# clock.net
KiCad netlist of a schematic drawn in Altium Designer
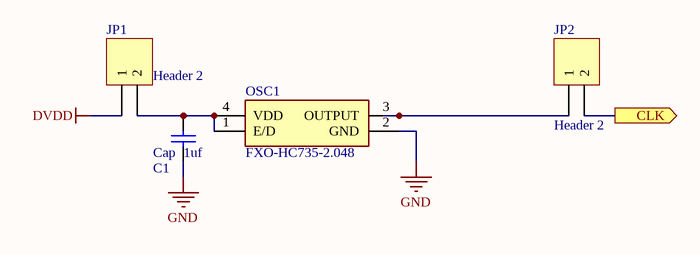
[diagram p0: clock.SchDoc]

(export (version "E")
  (design (tool "Eeschema 10.0.6"))
  (components
    (comp (ref "C1")
      (value "Cap")
      (footprint "1608[0603]")
      (description "Capacitor")
      (fields (field (name "ALTIUM_VALUE") "1uf") (field (name "PUBLISHER") "Altium Limited"))
      (libsource (lib "Miscellaneous Devices") (part "Cap"))
    )
    (comp (ref "JP1")
      (value "Header 2")
      (footprint "HDR1X2")
      (description "Header, 2-Pin")
      (fields (field (name "PUBLISHER") "Altium Limited"))
      (libsource (lib "Miscellaneous Connectors") (part "Header 2"))
    )
    (comp (ref "JP2")
      (value "Header 2")
      (footprint "HDR1X2")
      (description "Header, 2-Pin")
      (fields (field (name "PUBLISHER") "Altium Limited"))
      (libsource (lib "Miscellaneous Connectors") (part "Header 2"))
    )
    (comp (ref "OSC1")
      (value "FXO-HC735-2.048")
      (footprint "FXO-HC736R-40")
      (description "Crystal or Oscillator")
      (fields (field (name "MOUSER PART NUMBER") "XPO-HC735-2.048"))
      (libsource (lib "*") (part "FXO-HC735-2.048"))
    )
  )
  (nets
    (net (code "1") (name "/CLK") (class "Default")
      (node (ref "JP2") (pin "2") (pinfunction "2_2") (pintype "passive"))
    )
    (net (code "2") (name "DVDD") (class "Default")
      (node (ref "JP1") (pin "1") (pinfunction "1_1") (pintype "passive"))
    )
    (net (code "3") (name "GND") (class "Default")
      (node (ref "C1") (pin "1") (pinfunction "1_1") (pintype "passive"))
      (node (ref "OSC1") (pin "2") (pinfunction "GND_2") (pintype "passive"))
    )
    (net (code "4") (name "Net-(OSC1-E{slash}D)") (class "Default")
      (node (ref "C1") (pin "2") (pinfunction "2_2") (pintype "passive"))
      (node (ref "JP1") (pin "2") (pinfunction "2_2") (pintype "passive"))
      (node (ref "OSC1") (pin "1") (pinfunction "E/D_1") (pintype "passive"))
      (node (ref "OSC1") (pin "4") (pinfunction "VDD_4") (pintype "passive"))
    )
    (net (code "5") (name "Net-(OSC1-OUTPUT)") (class "Default")
      (node (ref "JP2") (pin "1") (pinfunction "1_1") (pintype "passive"))
      (node (ref "OSC1") (pin "3") (pinfunction "OUTPUT_3") (pintype "passive"))
    )
  )
)
